# controller.net
KiCad netlist of a schematic drawn in EAGLE
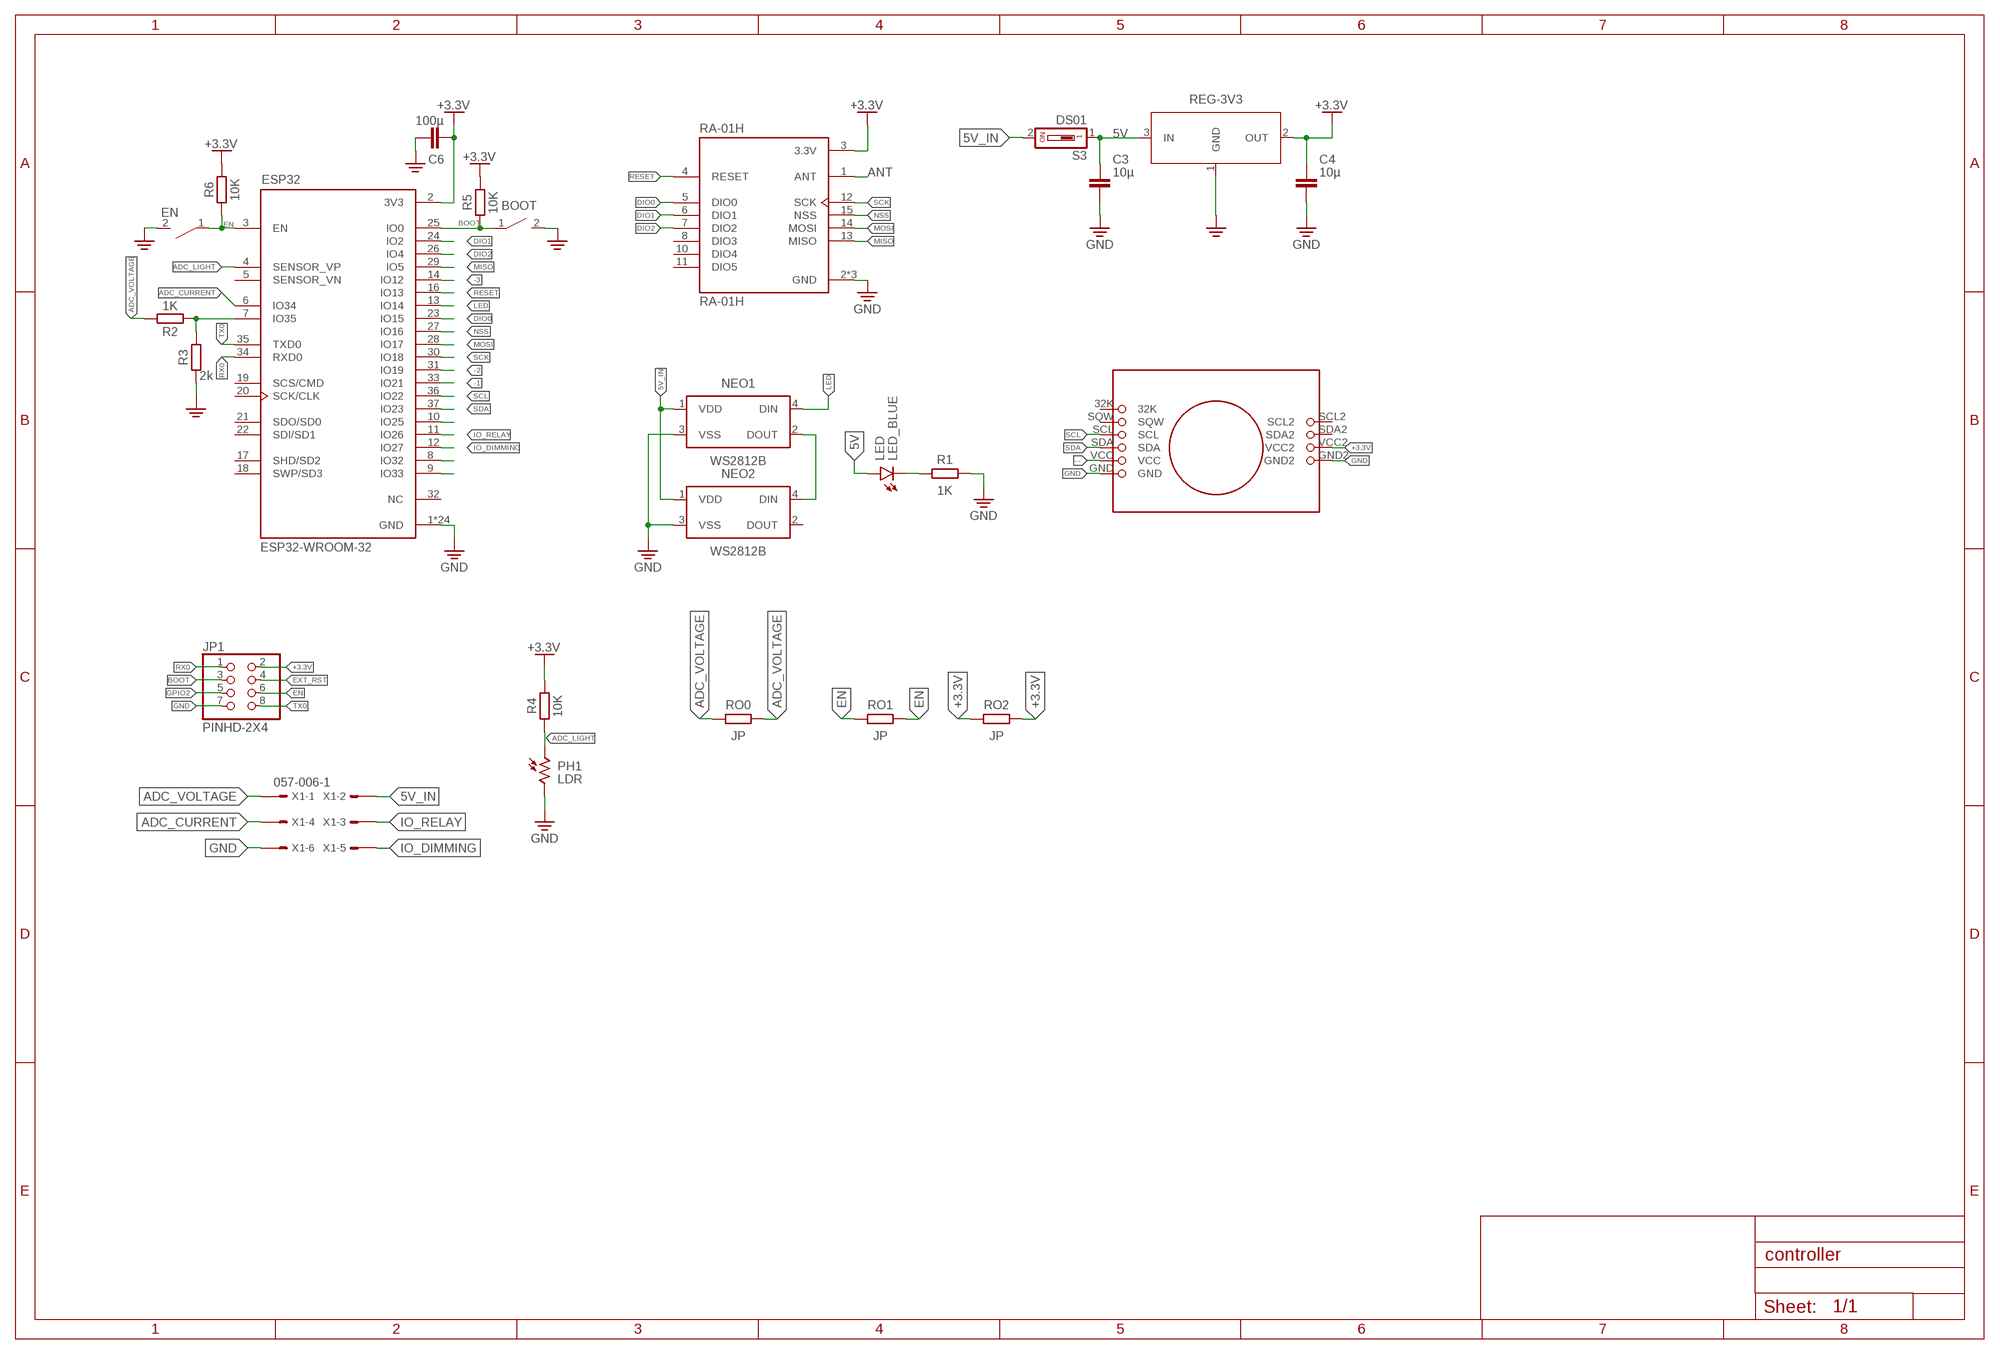
[diagram p0: schematic, sheet 1]

(export (version "E")
  (design (tool "Eeschema 10.0.6"))
  (components
    (comp (ref "BOOT")
      (value "B3U-X000B3U-1000P(M)1000P(M)")
      (footprint "eagle-import:B3U-1000P(M)")
      (fields (field (name "MANUFACTURER") "OMRON"))
      (libsource (lib "eagle-import") (part "B3U-X0001000P(M)B3U-1000P(M)"))
    )
    (comp (ref "C3")
      (value "10µ")
      (footprint "eagle-import:CAPC2012X110")
      (libsource (lib "eagle-import") (part "CCHIP-0805(2012-METRIC)_"))
    )
    (comp (ref "C4")
      (value "10µ")
      (footprint "eagle-import:CAPC2012X110")
      (libsource (lib "eagle-import") (part "CCHIP-0805(2012-METRIC)_"))
    )
    (comp (ref "C6")
      (value "100µ")
      (footprint "eagle-import:CAPM6032X280")
      (libsource (lib "eagle-import") (part "CTANTALUM-2412(6032-METRIC)_"))
    )
    (comp (ref "EN")
      (value "B3U-X000B3U-1000P(M)1000P(M)")
      (footprint "eagle-import:B3U-1000P(M)")
      (fields (field (name "MANUFACTURER") "OMRON"))
      (libsource (lib "eagle-import") (part "B3U-X0001000P(M)B3U-1000P(M)"))
    )
    (comp (ref "ESP32")
      (value "ESP32-WROOM-32")
      (footprint "eagle-import:MODULE_ESP32-WROOM-32")
      (fields (field (name "MANUFACTURER") "Espressif Systems"))
      (libsource (lib "eagle-import") (part "ESP32-WROOM-32"))
    )
    (comp (ref "JP1")
      (value "PINHD-2X4")
      (footprint "eagle-import:2X04")
      (libsource (lib "eagle-import") (part "PINHD-2X4"))
    )
    (comp (ref "LED")
      (value "LED_BLUE")
      (footprint "eagle-import:LEDC2012X110N_FLAT-B")
      (libsource (lib "eagle-import") (part "CHIP-FLAT-B_0805"))
    )
    (comp (ref "NEO1")
      (value "WS2812B")
      (footprint "eagle-import:WS2812B")
      (fields (field (name "MANUFACTURER") "Worldsemi"))
      (libsource (lib "eagle-import") (part "WS2812B"))
    )
    (comp (ref "NEO2")
      (value "WS2812B")
      (footprint "eagle-import:WS2812B")
      (fields (field (name "MANUFACTURER") "Worldsemi"))
      (libsource (lib "eagle-import") (part "WS2812B"))
    )
    (comp (ref "PH1")
      (value "LDR")
      (footprint "eagle-import:T0-46-A10XX")
      (libsource (lib "eagle-import") (part "A1050_09"))
    )
    (comp (ref "R1")
      (value "1K")
      (footprint "eagle-import:RESC2012X65")
      (libsource (lib "eagle-import") (part "RCHIP-0805(2012-METRIC)_"))
    )
    (comp (ref "R2")
      (value "1K")
      (footprint "eagle-import:RESC2012X65")
      (libsource (lib "eagle-import") (part "RCHIP-0805(2012-METRIC)_"))
    )
    (comp (ref "R3")
      (value "2k")
      (footprint "eagle-import:RESC2012X65")
      (libsource (lib "eagle-import") (part "RCHIP-0805(2012-METRIC)_"))
    )
    (comp (ref "R4")
      (value "10K")
      (footprint "eagle-import:RESC1608X60")
      (libsource (lib "eagle-import") (part "RCHIP-0603(1608-METRIC)_"))
    )
    (comp (ref "R5")
      (value "10K")
      (footprint "eagle-import:RESC2012X65")
      (libsource (lib "eagle-import") (part "RCHIP-0805(2012-METRIC)_"))
    )
    (comp (ref "R6")
      (value "10K")
      (footprint "eagle-import:RESC2012X65")
      (libsource (lib "eagle-import") (part "RCHIP-0805(2012-METRIC)_"))
    )
    (comp (ref "RA-01H")
      (value "RA-01H")
      (footprint "eagle-import:RA-01H")
      (fields (field (name "MANUFACTURER") "AI-Thinker"))
      (libsource (lib "eagle-import") (part "RA-01H"))
    )
    (comp (ref "REG-3V3")
      (value "NCP1117ST33T3G")
      (footprint "eagle-import:SOT230P700X170-4")
      (fields (field (name "MANUFACTURER") "ON Semiconductor"))
      (libsource (lib "eagle-import") (part "NCP1117ST33T3GSOT-223"))
    )
    (comp (ref "RO0")
      (value "JP")
      (footprint "eagle-import:RESC2012X65")
      (libsource (lib "eagle-import") (part "RCHIP-0805(2012-METRIC)_"))
    )
    (comp (ref "RO1")
      (value "JP")
      (footprint "eagle-import:RESC2012X65")
      (libsource (lib "eagle-import") (part "RCHIP-0805(2012-METRIC)_"))
    )
    (comp (ref "RO2")
      (value "JP")
      (footprint "eagle-import:RESC2012X65")
      (libsource (lib "eagle-import") (part "RCHIP-0805(2012-METRIC)_"))
    )
    (comp (ref "S3")
      (value "DS01")
      (footprint "eagle-import:DS-01")
      (libsource (lib "eagle-import") (part "DS01"))
    )
    (comp (ref "U$1")
      (value "DS3231_MODULE")
      (footprint "eagle-import:DS3231_MODULE")
      (libsource (lib "eagle-import") (part "DS3231_MODULE"))
    )
    (comp (ref "X1")
      (value "057-006-1")
      (footprint "eagle-import:057-006-1")
      (libsource (lib "eagle-import") (part "057-006-1"))
    )
  )
  (nets
    (net (code "1") (name "+3.3V") (class "Default")
      (node (ref "C4") (pin "1") (pinfunction "1_1") (pintype "passive"))
      (node (ref "C6") (pin "1") (pinfunction "1_1") (pintype "passive"))
      (node (ref "ESP32") (pin "2") (pinfunction "3V3_2") (pintype "power_in"))
      (node (ref "JP1") (pin "2") (pinfunction "2_2") (pintype "passive"))
      (node (ref "R4") (pin "2") (pinfunction "2_2") (pintype "passive"))
      (node (ref "R5") (pin "2") (pinfunction "2_2") (pintype "passive"))
      (node (ref "R6") (pin "2") (pinfunction "2_2") (pintype "passive"))
      (node (ref "RA-01H") (pin "3") (pinfunction "3.3V_3") (pintype "power_in"))
      (node (ref "REG-3V3") (pin "2") (pinfunction "OUT_2") (pintype "output"))
      (node (ref "RO2") (pin "1") (pinfunction "1_1") (pintype "passive"))
      (node (ref "RO2") (pin "2") (pinfunction "2_2") (pintype "passive"))
      (node (ref "U$1") (pin "VCC2") (pinfunction "VCC2_VCC2") (pintype "bidirectional"))
    )
    (net (code "2") (name "--") (class "Default")
      (node (ref "U$1") (pin "VCC") (pinfunction "VCC_VCC") (pintype "bidirectional"))
    )
    (net (code "3") (name "-1") (class "Default")
      (node (ref "ESP32") (pin "33") (pinfunction "IO21_33") (pintype "bidirectional"))
    )
    (net (code "4") (name "-2") (class "Default")
      (node (ref "ESP32") (pin "31") (pinfunction "IO19_31") (pintype "bidirectional"))
    )
    (net (code "5") (name "-3") (class "Default")
      (node (ref "ESP32") (pin "14") (pinfunction "IO12_14") (pintype "bidirectional"))
    )
    (net (code "6") (name "/ANT") (class "Default")
      (node (ref "RA-01H") (pin "1") (pinfunction "ANT_1") (pintype "bidirectional"))
    )
    (net (code "7") (name "5V") (class "Default")
      (node (ref "C3") (pin "1") (pinfunction "1_1") (pintype "passive"))
      (node (ref "LED") (pin "A") (pinfunction "A_A") (pintype "passive"))
      (node (ref "REG-3V3") (pin "3") (pinfunction "IN_3") (pintype "input"))
      (node (ref "S3") (pin "1") (pinfunction "1_1") (pintype "passive"))
    )
    (net (code "8") (name "5V_IN") (class "Default")
      (node (ref "NEO1") (pin "1") (pinfunction "VDD_1") (pintype "power_in"))
      (node (ref "NEO2") (pin "1") (pinfunction "VDD_1") (pintype "power_in"))
      (node (ref "S3") (pin "2") (pinfunction "2_2") (pintype "passive"))
      (node (ref "X1") (pin "2") (pinfunction "S_2") (pintype "passive"))
    )
    (net (code "9") (name "ADC_CURRENT") (class "Default")
      (node (ref "ESP32") (pin "6") (pinfunction "IO34_6") (pintype "input"))
      (node (ref "X1") (pin "4") (pinfunction "S_4") (pintype "passive"))
    )
    (net (code "10") (name "ADC_LIGHT") (class "Default")
      (node (ref "ESP32") (pin "4") (pinfunction "SENSOR_VP_4") (pintype "input"))
      (node (ref "PH1") (pin "1") (pinfunction "1_1") (pintype "passive"))
      (node (ref "R4") (pin "1") (pinfunction "1_1") (pintype "passive"))
    )
    (net (code "11") (name "ADC_VOLTAGE") (class "Default")
      (node (ref "R2") (pin "2") (pinfunction "2_2") (pintype "passive"))
      (node (ref "RO0") (pin "1") (pinfunction "1_1") (pintype "passive"))
      (node (ref "RO0") (pin "2") (pinfunction "2_2") (pintype "passive"))
      (node (ref "X1") (pin "1") (pinfunction "S_1") (pintype "passive"))
    )
    (net (code "12") (name "BOOT") (class "Default")
      (node (ref "BOOT") (pin "1") (pinfunction "1_1") (pintype "bidirectional"))
      (node (ref "ESP32") (pin "25") (pinfunction "IO0_25") (pintype "bidirectional"))
      (node (ref "JP1") (pin "3") (pinfunction "3_3") (pintype "passive"))
      (node (ref "R5") (pin "1") (pinfunction "1_1") (pintype "passive"))
    )
    (net (code "13") (name "DIO0") (class "Default")
      (node (ref "ESP32") (pin "23") (pinfunction "IO15_23") (pintype "bidirectional"))
      (node (ref "RA-01H") (pin "5") (pinfunction "DIO0_5") (pintype "bidirectional"))
    )
    (net (code "14") (name "DIO1") (class "Default")
      (node (ref "ESP32") (pin "24") (pinfunction "IO2_24") (pintype "bidirectional"))
      (node (ref "RA-01H") (pin "6") (pinfunction "DIO1_6") (pintype "bidirectional"))
    )
    (net (code "15") (name "DIO2") (class "Default")
      (node (ref "ESP32") (pin "26") (pinfunction "IO4_26") (pintype "bidirectional"))
      (node (ref "RA-01H") (pin "7") (pinfunction "DIO2_7") (pintype "bidirectional"))
    )
    (net (code "16") (name "EN") (class "Default")
      (node (ref "EN") (pin "1") (pinfunction "1_1") (pintype "bidirectional"))
      (node (ref "ESP32") (pin "3") (pinfunction "EN_3") (pintype "input"))
      (node (ref "JP1") (pin "6") (pinfunction "6_6") (pintype "passive"))
      (node (ref "R6") (pin "1") (pinfunction "1_1") (pintype "passive"))
      (node (ref "RO1") (pin "1") (pinfunction "1_1") (pintype "passive"))
      (node (ref "RO1") (pin "2") (pinfunction "2_2") (pintype "passive"))
    )
    (net (code "17") (name "EXT_RST") (class "Default")
      (node (ref "JP1") (pin "4") (pinfunction "4_4") (pintype "passive"))
    )
    (net (code "18") (name "GND") (class "Default")
      (node (ref "BOOT") (pin "2") (pinfunction "2_2") (pintype "bidirectional"))
      (node (ref "C3") (pin "2") (pinfunction "2_2") (pintype "passive"))
      (node (ref "C4") (pin "2") (pinfunction "2_2") (pintype "passive"))
      (node (ref "C6") (pin "2") (pinfunction "2_2") (pintype "passive"))
      (node (ref "EN") (pin "2") (pinfunction "2_2") (pintype "bidirectional"))
      (node (ref "ESP32") (pin "1") (pinfunction "GND_1") (pintype "power_in"))
      (node (ref "ESP32") (pin "15") (pinfunction "GND_15") (pintype "power_in"))
      (node (ref "ESP32") (pin "38") (pinfunction "GND_38") (pintype "power_in"))
      (node (ref "ESP32") (pin "39_1") (pinfunction "GND_39_1") (pintype "power_in"))
      (node (ref "ESP32") (pin "39_10") (pinfunction "GND_39_10") (pintype "power_in"))
      (node (ref "ESP32") (pin "39_11") (pinfunction "GND_39_11") (pintype "power_in"))
      (node (ref "ESP32") (pin "39_12") (pinfunction "GND_39_12") (pintype "power_in"))
      (node (ref "ESP32") (pin "39_13") (pinfunction "GND_39_13") (pintype "power_in"))
      (node (ref "ESP32") (pin "39_14") (pinfunction "GND_39_14") (pintype "power_in"))
      (node (ref "ESP32") (pin "39_15") (pinfunction "GND_39_15") (pintype "power_in"))
      (node (ref "ESP32") (pin "39_16") (pinfunction "GND_39_16") (pintype "power_in"))
      (node (ref "ESP32") (pin "39_17") (pinfunction "GND_39_17") (pintype "power_in"))
      (node (ref "ESP32") (pin "39_18") (pinfunction "GND_39_18") (pintype "power_in"))
      (node (ref "ESP32") (pin "39_19") (pinfunction "GND_39_19") (pintype "power_in"))
      (node (ref "ESP32") (pin "39_2") (pinfunction "GND_39_2") (pintype "power_in"))
      (node (ref "ESP32") (pin "39_20") (pinfunction "GND_39_20") (pintype "power_in"))
      (node (ref "ESP32") (pin "39_21") (pinfunction "GND_39_21") (pintype "power_in"))
      (node (ref "ESP32") (pin "39_3") (pinfunction "GND_39_3") (pintype "power_in"))
      (node (ref "ESP32") (pin "39_4") (pinfunction "GND_39_4") (pintype "power_in"))
      (node (ref "ESP32") (pin "39_5") (pinfunction "GND_39_5") (pintype "power_in"))
      (node (ref "ESP32") (pin "39_6") (pinfunction "GND_39_6") (pintype "power_in"))
      (node (ref "ESP32") (pin "39_7") (pinfunction "GND_39_7") (pintype "power_in"))
      (node (ref "ESP32") (pin "39_8") (pinfunction "GND_39_8") (pintype "power_in"))
      (node (ref "ESP32") (pin "39_9") (pinfunction "GND_39_9") (pintype "power_in"))
      (node (ref "JP1") (pin "7") (pinfunction "7_7") (pintype "passive"))
      (node (ref "NEO1") (pin "3") (pinfunction "VSS_3") (pintype "power_in"))
      (node (ref "NEO2") (pin "3") (pinfunction "VSS_3") (pintype "power_in"))
      (node (ref "PH1") (pin "2") (pinfunction "2_2") (pintype "passive"))
      (node (ref "R1") (pin "2") (pinfunction "2_2") (pintype "passive"))
      (node (ref "R3") (pin "1") (pinfunction "1_1") (pintype "passive"))
      (node (ref "RA-01H") (pin "16") (pinfunction "GND_16") (pintype "power_in"))
      (node (ref "RA-01H") (pin "2") (pinfunction "GND_2") (pintype "power_in"))
      (node (ref "RA-01H") (pin "9") (pinfunction "GND_9") (pintype "power_in"))
      (node (ref "REG-3V3") (pin "1") (pinfunction "GND_1") (pintype "passive"))
      (node (ref "U$1") (pin "GND") (pinfunction "GND_GND") (pintype "bidirectional"))
      (node (ref "U$1") (pin "GND2") (pinfunction "GND2_GND2") (pintype "bidirectional"))
      (node (ref "X1") (pin "6") (pinfunction "S_6") (pintype "passive"))
    )
    (net (code "19") (name "GPIO2") (class "Default")
      (node (ref "JP1") (pin "5") (pinfunction "5_5") (pintype "passive"))
    )
    (net (code "20") (name "IO_DIMMING") (class "Default")
      (node (ref "ESP32") (pin "12") (pinfunction "IO27_12") (pintype "bidirectional"))
      (node (ref "X1") (pin "5") (pinfunction "S_5") (pintype "passive"))
    )
    (net (code "21") (name "IO_RELAY") (class "Default")
      (node (ref "ESP32") (pin "11") (pinfunction "IO26_11") (pintype "bidirectional"))
      (node (ref "X1") (pin "3") (pinfunction "S_3") (pintype "passive"))
    )
    (net (code "22") (name "LED") (class "Default")
      (node (ref "ESP32") (pin "13") (pinfunction "IO14_13") (pintype "bidirectional"))
      (node (ref "NEO1") (pin "4") (pinfunction "DIN_4") (pintype "input"))
    )
    (net (code "23") (name "MISO") (class "Default")
      (node (ref "ESP32") (pin "29") (pinfunction "IO5_29") (pintype "bidirectional"))
      (node (ref "RA-01H") (pin "13") (pinfunction "MISO_13") (pintype "output"))
    )
    (net (code "24") (name "MOSI") (class "Default")
      (node (ref "ESP32") (pin "28") (pinfunction "IO17_28") (pintype "bidirectional"))
      (node (ref "RA-01H") (pin "14") (pinfunction "MOSI_14") (pintype "input"))
    )
    (net (code "25") (name "NSS") (class "Default")
      (node (ref "ESP32") (pin "27") (pinfunction "IO16_27") (pintype "bidirectional"))
      (node (ref "RA-01H") (pin "15") (pinfunction "NSS_15") (pintype "input"))
    )
    (net (code "26") (name "Net-(ESP32-IO35)") (class "Default")
      (node (ref "ESP32") (pin "7") (pinfunction "IO35_7") (pintype "input"))
      (node (ref "R2") (pin "1") (pinfunction "1_1") (pintype "passive"))
      (node (ref "R3") (pin "2") (pinfunction "2_2") (pintype "passive"))
    )
    (net (code "27") (name "Net-(LED-PadC)") (class "Default")
      (node (ref "LED") (pin "C") (pinfunction "C_C") (pintype "passive"))
      (node (ref "R1") (pin "1") (pinfunction "1_1") (pintype "passive"))
    )
    (net (code "28") (name "Net-(NEO1-DOUT)") (class "Default")
      (node (ref "NEO1") (pin "2") (pinfunction "DOUT_2") (pintype "output"))
      (node (ref "NEO2") (pin "4") (pinfunction "DIN_4") (pintype "input"))
    )
    (net (code "29") (name "RESET") (class "Default")
      (node (ref "ESP32") (pin "16") (pinfunction "IO13_16") (pintype "bidirectional"))
      (node (ref "RA-01H") (pin "4") (pinfunction "RESET_4") (pintype "input"))
    )
    (net (code "30") (name "RX0") (class "Default")
      (node (ref "ESP32") (pin "34") (pinfunction "RXD0_34") (pintype "bidirectional"))
      (node (ref "JP1") (pin "1") (pinfunction "1_1") (pintype "passive"))
    )
    (net (code "31") (name "SCK") (class "Default")
      (node (ref "ESP32") (pin "30") (pinfunction "IO18_30") (pintype "bidirectional"))
      (node (ref "RA-01H") (pin "12") (pinfunction "SCK_12") (pintype "input"))
    )
    (net (code "32") (name "SCL") (class "Default")
      (node (ref "ESP32") (pin "36") (pinfunction "IO22_36") (pintype "bidirectional"))
      (node (ref "U$1") (pin "SCL") (pinfunction "SCL_SCL") (pintype "bidirectional"))
    )
    (net (code "33") (name "SDA") (class "Default")
      (node (ref "ESP32") (pin "37") (pinfunction "IO23_37") (pintype "bidirectional"))
      (node (ref "U$1") (pin "SDA") (pinfunction "SDA_SDA") (pintype "bidirectional"))
    )
    (net (code "34") (name "TX0") (class "Default")
      (node (ref "ESP32") (pin "35") (pinfunction "TXD0_35") (pintype "bidirectional"))
      (node (ref "JP1") (pin "8") (pinfunction "8_8") (pintype "passive"))
    )
    (net (code "35") (name "unconnected-(ESP32-IO25-Pad10)") (class "Default")
      (node (ref "ESP32") (pin "10") (pinfunction "IO25_10") (pintype "bidirectional"))
    )
    (net (code "36") (name "unconnected-(ESP32-IO32-Pad8)") (class "Default")
      (node (ref "ESP32") (pin "8") (pinfunction "IO32_8") (pintype "bidirectional"))
    )
    (net (code "37") (name "unconnected-(ESP32-IO33-Pad9)") (class "Default")
      (node (ref "ESP32") (pin "9") (pinfunction "IO33_9") (pintype "bidirectional"))
    )
    (net (code "38") (name "unconnected-(ESP32-NC-Pad32)") (class "Default")
      (node (ref "ESP32") (pin "32") (pinfunction "NC_32") (pintype "no_connect"))
    )
    (net (code "39") (name "unconnected-(ESP32-SCK{slash}CLK-Pad20)") (class "Default")
      (node (ref "ESP32") (pin "20") (pinfunction "SCK/CLK_20") (pintype "bidirectional"))
    )
    (net (code "40") (name "unconnected-(ESP32-SCS{slash}CMD-Pad19)") (class "Default")
      (node (ref "ESP32") (pin "19") (pinfunction "SCS/CMD_19") (pintype "bidirectional"))
    )
    (net (code "41") (name "unconnected-(ESP32-SDI{slash}SD1-Pad22)") (class "Default")
      (node (ref "ESP32") (pin "22") (pinfunction "SDI/SD1_22") (pintype "bidirectional"))
    )
    (net (code "42") (name "unconnected-(ESP32-SDO{slash}SD0-Pad21)") (class "Default")
      (node (ref "ESP32") (pin "21") (pinfunction "SDO/SD0_21") (pintype "bidirectional"))
    )
    (net (code "43") (name "unconnected-(ESP32-SENSOR_VN-Pad5)") (class "Default")
      (node (ref "ESP32") (pin "5") (pinfunction "SENSOR_VN_5") (pintype "input"))
    )
    (net (code "44") (name "unconnected-(ESP32-SHD{slash}SD2-Pad17)") (class "Default")
      (node (ref "ESP32") (pin "17") (pinfunction "SHD/SD2_17") (pintype "bidirectional"))
    )
    (net (code "45") (name "unconnected-(ESP32-SWP{slash}SD3-Pad18)") (class "Default")
      (node (ref "ESP32") (pin "18") (pinfunction "SWP/SD3_18") (pintype "bidirectional"))
    )
    (net (code "46") (name "unconnected-(NEO2-DOUT-Pad2)") (class "Default")
      (node (ref "NEO2") (pin "2") (pinfunction "DOUT_2") (pintype "output"))
    )
    (net (code "47") (name "unconnected-(RA-01H-DIO3-Pad8)") (class "Default")
      (node (ref "RA-01H") (pin "8") (pinfunction "DIO3_8") (pintype "bidirectional"))
    )
    (net (code "48") (name "unconnected-(RA-01H-DIO4-Pad10)") (class "Default")
      (node (ref "RA-01H") (pin "10") (pinfunction "DIO4_10") (pintype "bidirectional"))
    )
    (net (code "49") (name "unconnected-(RA-01H-DIO5-Pad11)") (class "Default")
      (node (ref "RA-01H") (pin "11") (pinfunction "DIO5_11") (pintype "bidirectional"))
    )
    (net (code "50") (name "unconnected-(U$1-Pad32K)") (class "Default")
      (node (ref "U$1") (pin "32K") (pinfunction "32K_32K") (pintype "bidirectional"))
    )
    (net (code "51") (name "unconnected-(U$1-PadSCL2)") (class "Default")
      (node (ref "U$1") (pin "SCL2") (pinfunction "SCL2_SCL2") (pintype "bidirectional"))
    )
    (net (code "52") (name "unconnected-(U$1-PadSDA2)") (class "Default")
      (node (ref "U$1") (pin "SDA2") (pinfunction "SDA2_SDA2") (pintype "bidirectional"))
    )
    (net (code "53") (name "unconnected-(U$1-PadSQW)") (class "Default")
      (node (ref "U$1") (pin "SQW") (pinfunction "SQW_SQW") (pintype "bidirectional"))
    )
  )
)
